# Rocket-Control4.net
KiCad netlist of a schematic drawn in EAGLE
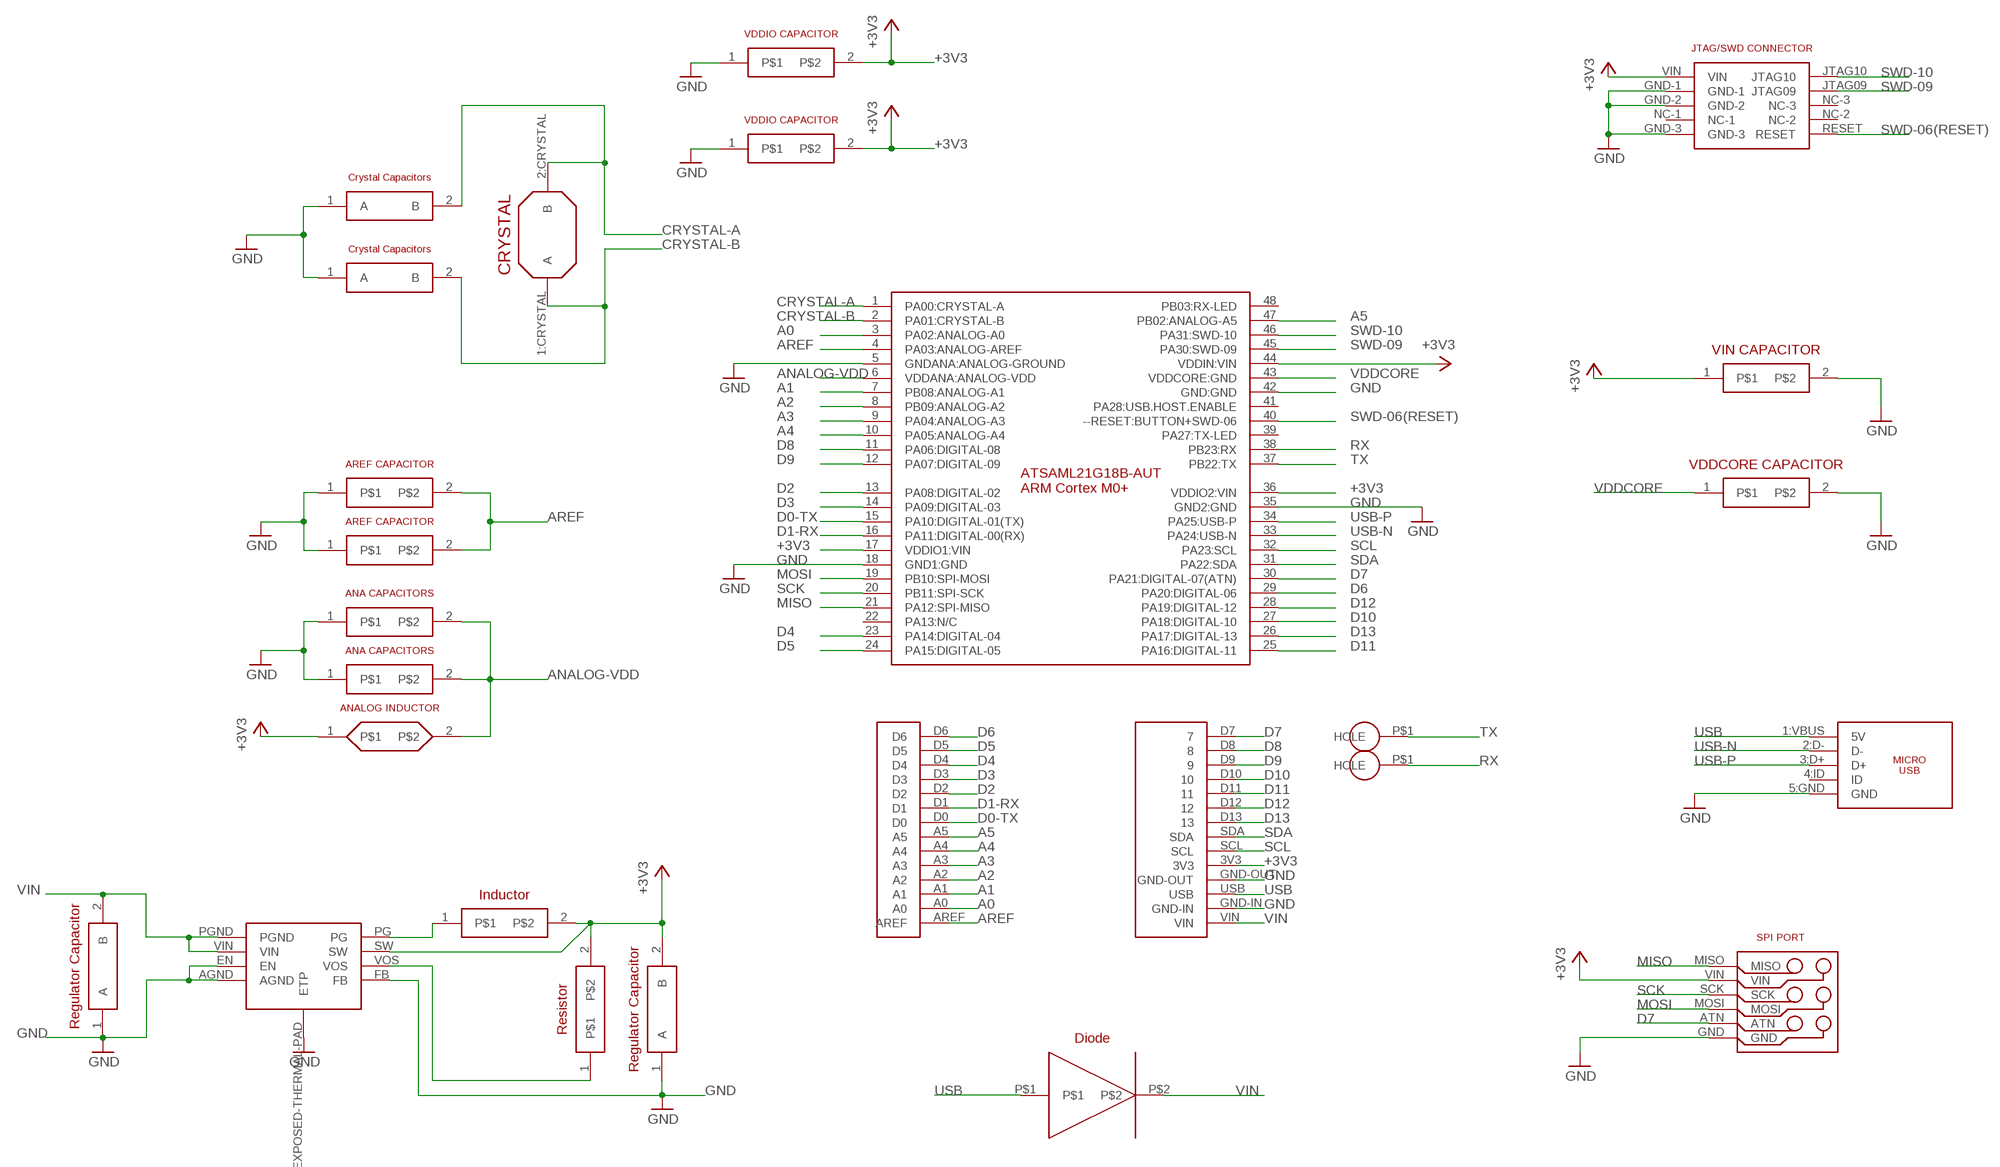
[diagram p0: schematic, sheet 1]

(export (version "E")
  (design (tool "Eeschema 10.0.6"))
  (components
    (comp (ref "U$1")
      (value "ATSAML21G18B-AUT")
      (footprint "eagle-import:TQFP48")
      (libsource (lib "eagle-import") (part "ATSAML21G18B-AUT"))
    )
    (comp (ref "U$2")
      (value "CRYSTAL-CAPACITORS")
      (footprint "eagle-import:C0603")
      (libsource (lib "eagle-import") (part "CRYSTAL-CAPACITORS"))
    )
    (comp (ref "U$3")
      (value "CRYSTAL-CAPACITORS")
      (footprint "eagle-import:C0603")
      (libsource (lib "eagle-import") (part "CRYSTAL-CAPACITORS"))
    )
    (comp (ref "U$4")
      (value "CRYSTAL")
      (footprint "eagle-import:4-SOJ_CRYSTAL")
      (libsource (lib "eagle-import") (part "CRYSTAL"))
    )
    (comp (ref "U$5")
      (value "REGULATOR")
      (footprint "eagle-import:8-WFDFN-EXPOSED-PAD")
      (libsource (lib "eagle-import") (part "REGULATOR"))
    )
    (comp (ref "U$6")
      (value "AREF-CAPACITORS")
      (footprint "eagle-import:C0402")
      (libsource (lib "eagle-import") (part "AREF-CAPACITORS"))
    )
    (comp (ref "U$7")
      (value "AREF-CAPACITORS")
      (footprint "eagle-import:C0402")
      (libsource (lib "eagle-import") (part "AREF-CAPACITORS"))
    )
    (comp (ref "U$8")
      (value "ANALOG-CAPACITORS")
      (footprint "eagle-import:C0402")
      (libsource (lib "eagle-import") (part "ANALOG-CAPACITORS"))
    )
    (comp (ref "U$9")
      (value "ANALOG-CAPACITORS")
      (footprint "eagle-import:C0402")
      (libsource (lib "eagle-import") (part "ANALOG-CAPACITORS"))
    )
    (comp (ref "U$10")
      (value "ANALOG-INDUCTOR")
      (footprint "eagle-import:C0603")
      (libsource (lib "eagle-import") (part "ANALOG-INDUCTOR"))
    )
    (comp (ref "U$11")
      (value "REGULATOR-CAPACITORS")
      (footprint "eagle-import:C0402")
      (libsource (lib "eagle-import") (part "REGULATOR-CAPACITORS"))
    )
    (comp (ref "U$12")
      (value "REGULATOR-CAPACITORS")
      (footprint "eagle-import:C0402")
      (libsource (lib "eagle-import") (part "REGULATOR-CAPACITORS"))
    )
    (comp (ref "U$13")
      (value "REGULATOR-INDUCTOR")
      (footprint "eagle-import:C0603")
      (libsource (lib "eagle-import") (part "REGULATOR-INDUCTOR"))
    )
    (comp (ref "U$14")
      (value "REGULATOR-RESISTOR")
      (footprint "eagle-import:C0603")
      (libsource (lib "eagle-import") (part "REGULATOR-RESISTOR"))
    )
    (comp (ref "U$15")
      (value "REGULATION-DIODE")
      (footprint "eagle-import:SOD-882")
      (libsource (lib "eagle-import") (part "REGULATION-DIODE"))
    )
    (comp (ref "U$16")
      (value "HEADER-HOLE")
      (footprint "eagle-import:HEADER-HOLE")
      (libsource (lib "eagle-import") (part "HEADER-HOLE"))
    )
    (comp (ref "U$17")
      (value "HEADER-HOLE")
      (footprint "eagle-import:HEADER-HOLE")
      (libsource (lib "eagle-import") (part "HEADER-HOLE"))
    )
    (comp (ref "U$21")
      (value "HEADER-SIDE-A")
      (footprint "eagle-import:HEADER-SIDE-A")
      (libsource (lib "eagle-import") (part "HEADER-SIDE-A"))
    )
    (comp (ref "U$22")
      (value "HEADER-SIDE-B")
      (footprint "eagle-import:HEADER-SIDE-B")
      (libsource (lib "eagle-import") (part "HEADER-SIDE-B"))
    )
    (comp (ref "U$26")
      (value "VDDIO-CAPACITOR")
      (footprint "eagle-import:C0402")
      (libsource (lib "eagle-import") (part "VDDIO-CAPACITOR"))
    )
    (comp (ref "U$35")
      (value "VDDIO-CAPACITOR")
      (footprint "eagle-import:C0402")
      (libsource (lib "eagle-import") (part "VDDIO-CAPACITOR"))
    )
    (comp (ref "U$38")
      (value "10118194-0001LF:MICRO-USB")
      (footprint "eagle-import:10118194-0001LF_MICRO-USB-B")
      (libsource (lib "eagle-import") (part "10118194-0001LF{colon}MICRO-USB"))
    )
    (comp (ref "U$41")
      (value "SPI-PORT")
      (footprint "eagle-import:SPI-PORT")
      (libsource (lib "eagle-import") (part "SPI-PORT"))
    )
    (comp (ref "U$56")
      (value "VDDCORE-CAPACITOR")
      (footprint "eagle-import:C0402")
      (libsource (lib "eagle-import") (part "VDDCORE-CAPACITOR"))
    )
    (comp (ref "U$57")
      (value "VIN-CAPACITOR")
      (footprint "eagle-import:C0402")
      (libsource (lib "eagle-import") (part "VIN-CAPACITOR"))
    )
    (comp (ref "U$61")
      (value "JTAG-MINI")
      (footprint "eagle-import:JTAG-MINI")
      (libsource (lib "eagle-import") (part "JTAG-MINI"))
    )
  )
  (nets
    (net (code "1") (name "+3V3") (class "Default")
      (node (ref "U$1") (pin "17") (pinfunction "VDDIO1:VIN_17") (pintype "bidirectional"))
      (node (ref "U$1") (pin "36") (pinfunction "VDDIO2:VIN_36") (pintype "bidirectional"))
      (node (ref "U$1") (pin "44") (pinfunction "VDDIN:VIN_44") (pintype "bidirectional"))
      (node (ref "U$10") (pin "1") (pinfunction "P$1_1") (pintype "bidirectional"))
      (node (ref "U$12") (pin "2") (pinfunction "B_2") (pintype "bidirectional"))
      (node (ref "U$13") (pin "2") (pinfunction "P$2_2") (pintype "bidirectional"))
      (node (ref "U$14") (pin "2") (pinfunction "P$2_2") (pintype "bidirectional"))
      (node (ref "U$22") (pin "3V3") (pinfunction "3V3_3V3") (pintype "bidirectional"))
      (node (ref "U$26") (pin "2") (pinfunction "P$2_2") (pintype "bidirectional"))
      (node (ref "U$35") (pin "2") (pinfunction "P$2_2") (pintype "bidirectional"))
      (node (ref "U$41") (pin "VIN") (pinfunction "VIN_VIN") (pintype "bidirectional"))
      (node (ref "U$5") (pin "SW") (pinfunction "SW_SW") (pintype "bidirectional"))
      (node (ref "U$57") (pin "1") (pinfunction "P$1_1") (pintype "bidirectional"))
      (node (ref "U$61") (pin "VIN") (pinfunction "VIN_VIN") (pintype "bidirectional"))
    )
    (net (code "2") (name "/A0") (class "Default")
      (node (ref "U$1") (pin "3") (pinfunction "PA02:ANALOG-A0_3") (pintype "bidirectional"))
      (node (ref "U$21") (pin "A0") (pinfunction "A0_A0") (pintype "bidirectional"))
    )
    (net (code "3") (name "/A1") (class "Default")
      (node (ref "U$1") (pin "7") (pinfunction "PB08:ANALOG-A1_7") (pintype "bidirectional"))
      (node (ref "U$21") (pin "A1") (pinfunction "A1_A1") (pintype "bidirectional"))
    )
    (net (code "4") (name "/A2") (class "Default")
      (node (ref "U$1") (pin "8") (pinfunction "PB09:ANALOG-A2_8") (pintype "bidirectional"))
      (node (ref "U$21") (pin "A2") (pinfunction "A2_A2") (pintype "bidirectional"))
    )
    (net (code "5") (name "/A3") (class "Default")
      (node (ref "U$1") (pin "9") (pinfunction "PA04:ANALOG-A3_9") (pintype "bidirectional"))
      (node (ref "U$21") (pin "A3") (pinfunction "A3_A3") (pintype "bidirectional"))
    )
    (net (code "6") (name "/A4") (class "Default")
      (node (ref "U$1") (pin "10") (pinfunction "PA05:ANALOG-A4_10") (pintype "bidirectional"))
      (node (ref "U$21") (pin "A4") (pinfunction "A4_A4") (pintype "bidirectional"))
    )
    (net (code "7") (name "/A5") (class "Default")
      (node (ref "U$1") (pin "47") (pinfunction "PB02:ANALOG-A5_47") (pintype "bidirectional"))
      (node (ref "U$21") (pin "A5") (pinfunction "A5_A5") (pintype "bidirectional"))
    )
    (net (code "8") (name "/ANALOG-VDD") (class "Default")
      (node (ref "U$1") (pin "6") (pinfunction "VDDANA:ANALOG-VDD_6") (pintype "bidirectional"))
      (node (ref "U$10") (pin "2") (pinfunction "P$2_2") (pintype "bidirectional"))
      (node (ref "U$8") (pin "2") (pinfunction "P$2_2") (pintype "bidirectional"))
      (node (ref "U$9") (pin "2") (pinfunction "P$2_2") (pintype "bidirectional"))
    )
    (net (code "9") (name "/AREF") (class "Default")
      (node (ref "U$1") (pin "4") (pinfunction "PA03:ANALOG-AREF_4") (pintype "bidirectional"))
      (node (ref "U$21") (pin "AREF") (pinfunction "AREF_AREF") (pintype "bidirectional"))
      (node (ref "U$6") (pin "2") (pinfunction "P$2_2") (pintype "bidirectional"))
      (node (ref "U$7") (pin "2") (pinfunction "P$2_2") (pintype "bidirectional"))
    )
    (net (code "10") (name "/CRYSTAL-A") (class "Default")
      (node (ref "U$1") (pin "1") (pinfunction "PA00:CRYSTAL-A_1") (pintype "bidirectional"))
      (node (ref "U$2") (pin "2") (pinfunction "B_2") (pintype "bidirectional"))
      (node (ref "U$4") (pin "2:CRYSTAL") (pinfunction "B_2:CRYSTAL") (pintype "bidirectional"))
    )
    (net (code "11") (name "/CRYSTAL-B") (class "Default")
      (node (ref "U$1") (pin "2") (pinfunction "PA01:CRYSTAL-B_2") (pintype "bidirectional"))
      (node (ref "U$3") (pin "2") (pinfunction "B_2") (pintype "bidirectional"))
      (node (ref "U$4") (pin "1:CRYSTAL") (pinfunction "A_1:CRYSTAL") (pintype "bidirectional"))
    )
    (net (code "12") (name "/D0-TX") (class "Default")
      (node (ref "U$1") (pin "15") (pinfunction "PA10:DIGITAL-01(TX)_15") (pintype "bidirectional"))
      (node (ref "U$21") (pin "D0") (pinfunction "D0_D0") (pintype "bidirectional"))
    )
    (net (code "13") (name "/D1-RX") (class "Default")
      (node (ref "U$1") (pin "16") (pinfunction "PA11:DIGITAL-00(RX)_16") (pintype "bidirectional"))
      (node (ref "U$21") (pin "D1") (pinfunction "D1_D1") (pintype "bidirectional"))
    )
    (net (code "14") (name "/D2") (class "Default")
      (node (ref "U$1") (pin "13") (pinfunction "PA08:DIGITAL-02_13") (pintype "bidirectional"))
      (node (ref "U$21") (pin "D2") (pinfunction "D2_D2") (pintype "bidirectional"))
    )
    (net (code "15") (name "/D3") (class "Default")
      (node (ref "U$1") (pin "14") (pinfunction "PA09:DIGITAL-03_14") (pintype "bidirectional"))
      (node (ref "U$21") (pin "D3") (pinfunction "D3_D3") (pintype "bidirectional"))
    )
    (net (code "16") (name "/D4") (class "Default")
      (node (ref "U$1") (pin "23") (pinfunction "PA14:DIGITAL-04_23") (pintype "bidirectional"))
      (node (ref "U$21") (pin "D4") (pinfunction "D4_D4") (pintype "bidirectional"))
    )
    (net (code "17") (name "/D5") (class "Default")
      (node (ref "U$1") (pin "24") (pinfunction "PA15:DIGITAL-05_24") (pintype "bidirectional"))
      (node (ref "U$21") (pin "D5") (pinfunction "D5_D5") (pintype "bidirectional"))
    )
    (net (code "18") (name "/D6") (class "Default")
      (node (ref "U$1") (pin "29") (pinfunction "PA20:DIGITAL-06_29") (pintype "bidirectional"))
      (node (ref "U$21") (pin "D6") (pinfunction "D6_D6") (pintype "bidirectional"))
    )
    (net (code "19") (name "/D7") (class "Default")
      (node (ref "U$1") (pin "30") (pinfunction "PA21:DIGITAL-07(ATN)_30") (pintype "bidirectional"))
      (node (ref "U$22") (pin "D7") (pinfunction "7_D7") (pintype "bidirectional"))
      (node (ref "U$41") (pin "ATN") (pinfunction "ATN_ATN") (pintype "bidirectional"))
    )
    (net (code "20") (name "/D8") (class "Default")
      (node (ref "U$1") (pin "11") (pinfunction "PA06:DIGITAL-08_11") (pintype "bidirectional"))
      (node (ref "U$22") (pin "D8") (pinfunction "8_D8") (pintype "bidirectional"))
    )
    (net (code "21") (name "/D9") (class "Default")
      (node (ref "U$1") (pin "12") (pinfunction "PA07:DIGITAL-09_12") (pintype "bidirectional"))
      (node (ref "U$22") (pin "D9") (pinfunction "9_D9") (pintype "bidirectional"))
    )
    (net (code "22") (name "/D10") (class "Default")
      (node (ref "U$1") (pin "27") (pinfunction "PA18:DIGITAL-10_27") (pintype "bidirectional"))
      (node (ref "U$22") (pin "D10") (pinfunction "10_D10") (pintype "bidirectional"))
    )
    (net (code "23") (name "/D11") (class "Default")
      (node (ref "U$1") (pin "25") (pinfunction "PA16:DIGITAL-11_25") (pintype "bidirectional"))
      (node (ref "U$22") (pin "D11") (pinfunction "11_D11") (pintype "bidirectional"))
    )
    (net (code "24") (name "/D12") (class "Default")
      (node (ref "U$1") (pin "28") (pinfunction "PA19:DIGITAL-12_28") (pintype "bidirectional"))
      (node (ref "U$22") (pin "D12") (pinfunction "12_D12") (pintype "bidirectional"))
    )
    (net (code "25") (name "/D13") (class "Default")
      (node (ref "U$1") (pin "26") (pinfunction "PA17:DIGITAL-13_26") (pintype "bidirectional"))
      (node (ref "U$22") (pin "D13") (pinfunction "13_D13") (pintype "bidirectional"))
    )
    (net (code "26") (name "/MISO") (class "Default")
      (node (ref "U$1") (pin "21") (pinfunction "PA12:SPI-MISO_21") (pintype "bidirectional"))
      (node (ref "U$41") (pin "MISO") (pinfunction "MISO_MISO") (pintype "bidirectional"))
    )
    (net (code "27") (name "/MOSI") (class "Default")
      (node (ref "U$1") (pin "19") (pinfunction "PB10:SPI-MOSI_19") (pintype "bidirectional"))
      (node (ref "U$41") (pin "MOSI") (pinfunction "MOSI_MOSI") (pintype "bidirectional"))
    )
    (net (code "28") (name "/RX") (class "Default")
      (node (ref "U$1") (pin "38") (pinfunction "PB23:RX_38") (pintype "bidirectional"))
      (node (ref "U$17") (pin "P$1") (pinfunction "HOLE_P$1") (pintype "bidirectional"))
    )
    (net (code "29") (name "/SCK") (class "Default")
      (node (ref "U$1") (pin "20") (pinfunction "PB11:SPI-SCK_20") (pintype "bidirectional"))
      (node (ref "U$41") (pin "SCK") (pinfunction "SCK_SCK") (pintype "bidirectional"))
    )
    (net (code "30") (name "/SCL") (class "Default")
      (node (ref "U$1") (pin "32") (pinfunction "PA23:SCL_32") (pintype "bidirectional"))
      (node (ref "U$22") (pin "SCL") (pinfunction "SCL_SCL") (pintype "bidirectional"))
    )
    (net (code "31") (name "/SDA") (class "Default")
      (node (ref "U$1") (pin "31") (pinfunction "PA22:SDA_31") (pintype "bidirectional"))
      (node (ref "U$22") (pin "SDA") (pinfunction "SDA_SDA") (pintype "bidirectional"))
    )
    (net (code "32") (name "/SWD-06(RESET)") (class "Default")
      (node (ref "U$1") (pin "40") (pinfunction "--RESET:BUTTON+SWD-06_40") (pintype "bidirectional"))
      (node (ref "U$61") (pin "RESET") (pinfunction "RESET_RESET") (pintype "bidirectional"))
    )
    (net (code "33") (name "/SWD-09") (class "Default")
      (node (ref "U$1") (pin "45") (pinfunction "PA30:SWD-09_45") (pintype "bidirectional"))
      (node (ref "U$61") (pin "JTAG09") (pinfunction "JTAG09_JTAG09") (pintype "bidirectional"))
    )
    (net (code "34") (name "/SWD-10") (class "Default")
      (node (ref "U$1") (pin "46") (pinfunction "PA31:SWD-10_46") (pintype "bidirectional"))
      (node (ref "U$61") (pin "JTAG10") (pinfunction "JTAG10_JTAG10") (pintype "bidirectional"))
    )
    (net (code "35") (name "/TX") (class "Default")
      (node (ref "U$1") (pin "37") (pinfunction "PB22:TX_37") (pintype "bidirectional"))
      (node (ref "U$16") (pin "P$1") (pinfunction "HOLE_P$1") (pintype "bidirectional"))
    )
    (net (code "36") (name "/USB") (class "Default")
      (node (ref "U$15") (pin "P$1") (pinfunction "P$1_P$1") (pintype "bidirectional"))
      (node (ref "U$22") (pin "USB") (pinfunction "USB_USB") (pintype "bidirectional"))
      (node (ref "U$38") (pin "1:VBUS") (pinfunction "5V_1:VBUS") (pintype "bidirectional"))
    )
    (net (code "37") (name "/USB-N") (class "Default")
      (node (ref "U$1") (pin "33") (pinfunction "PA24:USB-N_33") (pintype "bidirectional"))
      (node (ref "U$38") (pin "2:D-") (pinfunction "D-_2:D-") (pintype "bidirectional"))
    )
    (net (code "38") (name "/USB-P") (class "Default")
      (node (ref "U$1") (pin "34") (pinfunction "PA25:USB-P_34") (pintype "bidirectional"))
      (node (ref "U$38") (pin "3:D+") (pinfunction "D+_3:D+") (pintype "bidirectional"))
    )
    (net (code "39") (name "/VDDCORE") (class "Default")
      (node (ref "U$1") (pin "43") (pinfunction "VDDCORE:GND_43") (pintype "bidirectional"))
      (node (ref "U$56") (pin "1") (pinfunction "P$1_1") (pintype "bidirectional"))
    )
    (net (code "40") (name "/VIN") (class "Default")
      (node (ref "U$11") (pin "2") (pinfunction "B_2") (pintype "bidirectional"))
      (node (ref "U$15") (pin "P$2") (pinfunction "P$2_P$2") (pintype "bidirectional"))
      (node (ref "U$22") (pin "VIN") (pinfunction "VIN_VIN") (pintype "bidirectional"))
      (node (ref "U$5") (pin "PGND") (pinfunction "PGND_PGND") (pintype "bidirectional"))
      (node (ref "U$5") (pin "VIN") (pinfunction "VIN_VIN") (pintype "bidirectional"))
    )
    (net (code "41") (name "GND") (class "Default")
      (node (ref "U$1") (pin "18") (pinfunction "GND1:GND_18") (pintype "bidirectional"))
      (node (ref "U$1") (pin "35") (pinfunction "GND2:GND_35") (pintype "bidirectional"))
      (node (ref "U$1") (pin "42") (pinfunction "GND:GND_42") (pintype "bidirectional"))
      (node (ref "U$1") (pin "5") (pinfunction "GNDANA:ANALOG-GROUND_5") (pintype "bidirectional"))
      (node (ref "U$11") (pin "1") (pinfunction "A_1") (pintype "bidirectional"))
      (node (ref "U$12") (pin "1") (pinfunction "A_1") (pintype "bidirectional"))
      (node (ref "U$2") (pin "1") (pinfunction "A_1") (pintype "bidirectional"))
      (node (ref "U$22") (pin "GND-IN") (pinfunction "GND-IN_GND-IN") (pintype "bidirectional"))
      (node (ref "U$22") (pin "GND-OUT") (pinfunction "GND-OUT_GND-OUT") (pintype "bidirectional"))
      (node (ref "U$26") (pin "1") (pinfunction "P$1_1") (pintype "bidirectional"))
      (node (ref "U$3") (pin "1") (pinfunction "A_1") (pintype "bidirectional"))
      (node (ref "U$35") (pin "1") (pinfunction "P$1_1") (pintype "bidirectional"))
      (node (ref "U$38") (pin "5:GND") (pinfunction "GND_5:GND") (pintype "bidirectional"))
      (node (ref "U$41") (pin "GND") (pinfunction "GND_GND") (pintype "bidirectional"))
      (node (ref "U$5") (pin "AGND") (pinfunction "AGND_AGND") (pintype "bidirectional"))
      (node (ref "U$5") (pin "EN") (pinfunction "EN_EN") (pintype "bidirectional"))
      (node (ref "U$5") (pin "EXPOSED-THERMAL-PAD") (pinfunction "ETP_EXPOSED-THERMAL-PAD") (pintype "bidirectional"))
      (node (ref "U$5") (pin "FB") (pinfunction "FB_FB") (pintype "bidirectional"))
      (node (ref "U$56") (pin "2") (pinfunction "P$2_2") (pintype "bidirectional"))
      (node (ref "U$57") (pin "2") (pinfunction "P$2_2") (pintype "bidirectional"))
      (node (ref "U$6") (pin "1") (pinfunction "P$1_1") (pintype "bidirectional"))
      (node (ref "U$61") (pin "GND-1") (pinfunction "GND-1_GND-1") (pintype "bidirectional"))
      (node (ref "U$61") (pin "GND-2") (pinfunction "GND-2_GND-2") (pintype "bidirectional"))
      (node (ref "U$61") (pin "GND-3") (pinfunction "GND-3_GND-3") (pintype "bidirectional"))
      (node (ref "U$7") (pin "1") (pinfunction "P$1_1") (pintype "bidirectional"))
      (node (ref "U$8") (pin "1") (pinfunction "P$1_1") (pintype "bidirectional"))
      (node (ref "U$9") (pin "1") (pinfunction "P$1_1") (pintype "bidirectional"))
    )
    (net (code "42") (name "Net-(U$13-P$1)") (class "Default")
      (node (ref "U$13") (pin "1") (pinfunction "P$1_1") (pintype "bidirectional"))
      (node (ref "U$5") (pin "PG") (pinfunction "PG_PG") (pintype "bidirectional"))
    )
    (net (code "43") (name "Net-(U$14-P$1)") (class "Default")
      (node (ref "U$14") (pin "1") (pinfunction "P$1_1") (pintype "bidirectional"))
      (node (ref "U$5") (pin "VOS") (pinfunction "VOS_VOS") (pintype "bidirectional"))
    )
    (net (code "44") (name "unconnected-(U$1-PA13:N{slash}C-Pad22)") (class "Default")
      (node (ref "U$1") (pin "22") (pinfunction "PA13:N/C_22") (pintype "bidirectional"))
    )
    (net (code "45") (name "unconnected-(U$1-PA27:TX-LED-Pad39)") (class "Default")
      (node (ref "U$1") (pin "39") (pinfunction "PA27:TX-LED_39") (pintype "bidirectional"))
    )
    (net (code "46") (name "unconnected-(U$1-PA28:USB.HOST.ENABLE-Pad41)") (class "Default")
      (node (ref "U$1") (pin "41") (pinfunction "PA28:USB.HOST.ENABLE_41") (pintype "bidirectional"))
    )
    (net (code "47") (name "unconnected-(U$1-PB03:RX-LED-Pad48)") (class "Default")
      (node (ref "U$1") (pin "48") (pinfunction "PB03:RX-LED_48") (pintype "bidirectional"))
    )
    (net (code "48") (name "unconnected-(U$38-ID-Pad4:ID)") (class "Default")
      (node (ref "U$38") (pin "4:ID") (pinfunction "ID_4:ID") (pintype "bidirectional"))
    )
    (net (code "49") (name "unconnected-(U$61-PadNC-1)") (class "Default")
      (node (ref "U$61") (pin "NC-1") (pinfunction "NC-1_NC-1") (pintype "bidirectional"))
    )
    (net (code "50") (name "unconnected-(U$61-PadNC-2)") (class "Default")
      (node (ref "U$61") (pin "NC-2") (pinfunction "NC-2_NC-2") (pintype "bidirectional"))
    )
    (net (code "51") (name "unconnected-(U$61-PadNC-3)") (class "Default")
      (node (ref "U$61") (pin "NC-3") (pinfunction "NC-3_NC-3") (pintype "bidirectional"))
    )
  )
)
